# Controller.net
KiCad netlist of a schematic drawn in Altium Designer
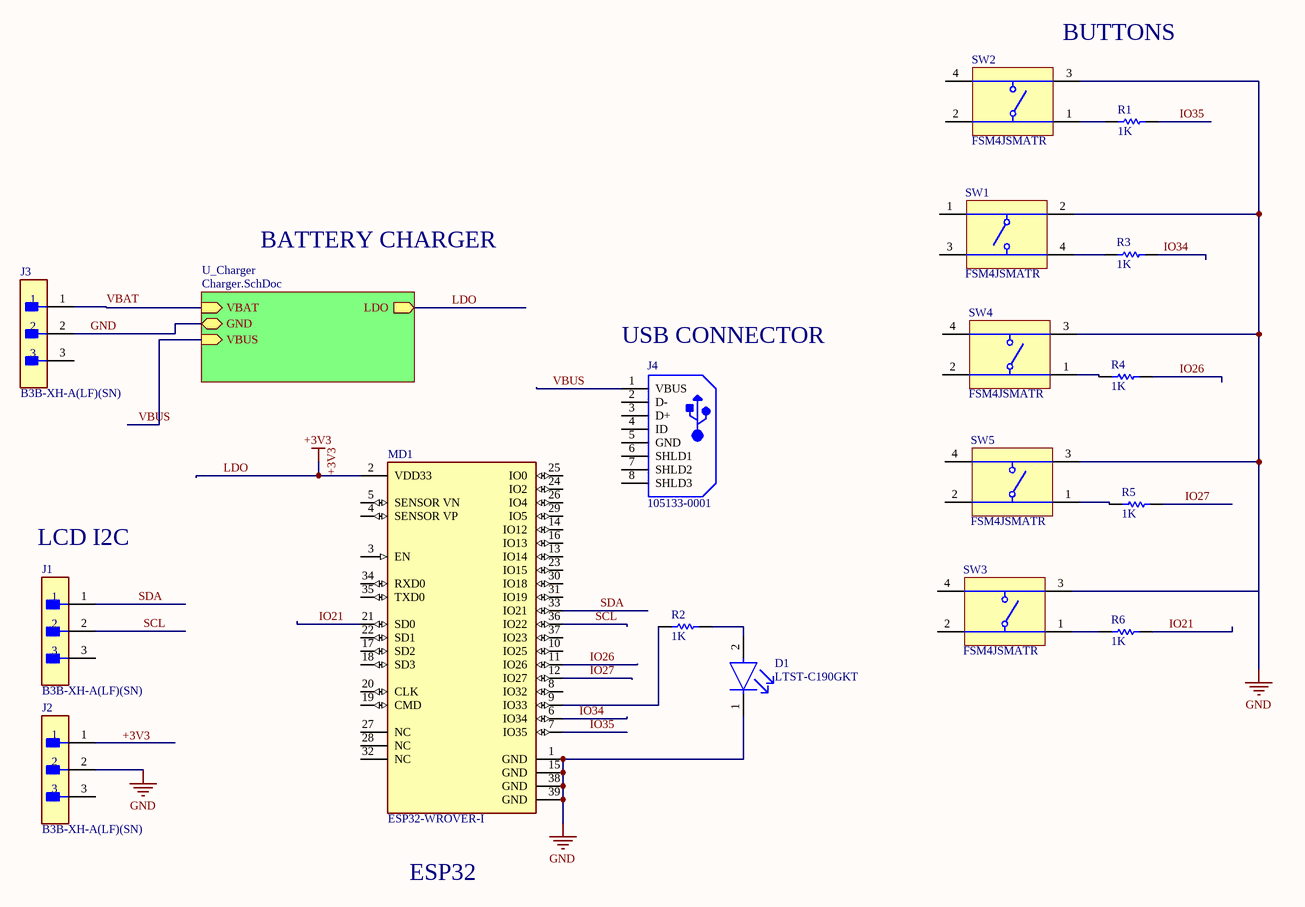
[diagram p0: Controller.SchDoc]

(export (version "E")
  (design (tool "Eeschema 10.0.6"))
  (components
    (comp (ref "D1")
      (value "LTST-C190GKT")
      (footprint "FP-LTST-C190GKT-MFG")
      (description "LED GREEN CLEAR CHIP SMD")
      (fields (field (name "VOLTAGE") "2V"))
      (libsource (lib "Altium Content Vault") (part "8706943c75ba83719d021d2fdc84c58"))
    )
    (comp (ref "J1")
      (value "B3B-XH-A(LF)(SN)")
      (footprint "FP-B3B-XH-A_LF_SN-MFG")
      (description "CONN HEADER VERT 3POS 2.5MM")
      (libsource (lib "Altium Content Vault") (part "0d3f023dd272f625e17a2be33dea85f"))
    )
    (comp (ref "J2")
      (value "B3B-XH-A(LF)(SN)")
      (footprint "FP-B3B-XH-A_LF_SN-MFG")
      (description "CONN HEADER VERT 3POS 2.5MM")
      (libsource (lib "Altium Content Vault") (part "0d3f023dd272f625e17a2be33dea85f"))
    )
    (comp (ref "J3")
      (value "B3B-XH-A(LF)(SN)")
      (footprint "FP-B3B-XH-A_LF_SN-MFG")
      (description "CONN HEADER VERT 3POS 2.5MM")
      (libsource (lib "Altium Content Vault") (part "0d3f023dd272f625e17a2be33dea85f"))
    )
    (comp (ref "J4")
      (value "105133-0001")
      (footprint "MOLX-105133-0001_V")
      (description "Micro-USB B Receptacle, Vertical, -30 to 85 degC, 5-Pin SMD, RoHS, Tape and Reel")
      (fields (field (name "MANUFACTURER") "Molex"))
      (libsource (lib "Altium Content Vault") (part "USB-5-3SHLD"))
    )
    (comp (ref "MD1")
      (value "ESP32-WROVER-I")
      (footprint "FP-ESP32-WROVER-I-MFG")
      (description "SMD MODULE, ESP32-D0WDQ6, 32MBIT")
      (fields
        (field (name "MANUFACTURER") "Espressif")
        (field (name "OCTOPART") "https://octopart.com/esp32-wrover-i-espressif+systems-89171349")
      )
      (libsource (lib "Altium Content Vault") (part "cbbb37af8bcfe61dfd46ac9418f0340"))
    )
    (comp (ref "R1")
      (value "1K")
      (footprint "RESC2013X65X40LL15T20")
      (description "Chip Resistor, 0 Ohm, 0.125 W, -55 to 125 degC, 0805 (2012 Metric), RoHS, Tape and Reel")
      (fields (field (name "TOLERANCE") "0%") (field (name "MANUFACTURER") "TE Connectivity"))
      (libsource (lib "Altium Content Vault") (part "RES-2"))
    )
    (comp (ref "R2")
      (value "1K")
      (footprint "RESC2013X65X40LL15T20")
      (description "Chip Resistor, 0 Ohm, 0.125 W, -55 to 125 degC, 0805 (2012 Metric), RoHS, Tape and Reel")
      (fields (field (name "TOLERANCE") "0%") (field (name "MANUFACTURER") "TE Connectivity"))
      (libsource (lib "Altium Content Vault") (part "RES-2"))
    )
    (comp (ref "R3")
      (value "1K")
      (footprint "RESC2013X65X40LL15T20")
      (description "Chip Resistor, 0 Ohm, 0.125 W, -55 to 125 degC, 0805 (2012 Metric), RoHS, Tape and Reel")
      (fields (field (name "TOLERANCE") "0%") (field (name "MANUFACTURER") "TE Connectivity"))
      (libsource (lib "Altium Content Vault") (part "RES-2"))
    )
    (comp (ref "R4")
      (value "1K")
      (footprint "RESC2013X65X40LL15T20")
      (description "Chip Resistor, 0 Ohm, 0.125 W, -55 to 125 degC, 0805 (2012 Metric), RoHS, Tape and Reel")
      (fields (field (name "TOLERANCE") "0%") (field (name "MANUFACTURER") "TE Connectivity"))
      (libsource (lib "Altium Content Vault") (part "RES-2"))
    )
    (comp (ref "R5")
      (value "1K")
      (footprint "RESC2013X65X40LL15T20")
      (description "Chip Resistor, 0 Ohm, 0.125 W, -55 to 125 degC, 0805 (2012 Metric), RoHS, Tape and Reel")
      (fields (field (name "TOLERANCE") "0%") (field (name "MANUFACTURER") "TE Connectivity"))
      (libsource (lib "Altium Content Vault") (part "RES-2"))
    )
    (comp (ref "R6")
      (value "1K")
      (footprint "RESC2013X65X40LL15T20")
      (description "Chip Resistor, 0 Ohm, 0.125 W, -55 to 125 degC, 0805 (2012 Metric), RoHS, Tape and Reel")
      (fields (field (name "TOLERANCE") "0%") (field (name "MANUFACTURER") "TE Connectivity"))
      (libsource (lib "Altium Content Vault") (part "RES-2"))
    )
    (comp (ref "SW1")
      (value "FSM4JSMATR")
      (footprint "TECO-FSM4JSMATR_V")
      (description "Micro Miniature Push Button Switch FSM JSM, 50 mA, -35 to 85 degC, 4-Pin SMD, RoHS, Tape and Reel")
      (fields (field (name "MANUFACTURER") "TE Connectivity"))
      (libsource (lib "") (part "SW-SPST-4_A_1"))
    )
    (comp (ref "SW2")
      (value "FSM4JSMATR")
      (footprint "TECO-FSM4JSMATR_V")
      (description "Micro Miniature Push Button Switch FSM JSM, 50 mA, -35 to 85 degC, 4-Pin SMD, RoHS, Tape and Reel")
      (fields (field (name "MANUFACTURER") "TE Connectivity"))
      (libsource (lib "Altium Content Vault") (part "SW-SPST-4_A"))
    )
    (comp (ref "SW3")
      (value "FSM4JSMATR")
      (footprint "TECO-FSM4JSMATR_V")
      (description "Micro Miniature Push Button Switch FSM JSM, 50 mA, -35 to 85 degC, 4-Pin SMD, RoHS, Tape and Reel")
      (fields (field (name "MANUFACTURER") "TE Connectivity"))
      (libsource (lib "Altium Content Vault") (part "SW-SPST-4_A"))
    )
    (comp (ref "SW4")
      (value "FSM4JSMATR")
      (footprint "TECO-FSM4JSMATR_V")
      (description "Micro Miniature Push Button Switch FSM JSM, 50 mA, -35 to 85 degC, 4-Pin SMD, RoHS, Tape and Reel")
      (fields (field (name "MANUFACTURER") "TE Connectivity"))
      (libsource (lib "Altium Content Vault") (part "SW-SPST-4_A"))
    )
    (comp (ref "SW5")
      (value "FSM4JSMATR")
      (footprint "TECO-FSM4JSMATR_V")
      (description "Micro Miniature Push Button Switch FSM JSM, 50 mA, -35 to 85 degC, 4-Pin SMD, RoHS, Tape and Reel")
      (fields (field (name "MANUFACTURER") "TE Connectivity"))
      (libsource (lib "Altium Content Vault") (part "SW-SPST-4_A"))
    )
  )
  (nets
    (net (code "1") (name "+3V3") (class "Default")
      (node (ref "MD1") (pin "2") (pinfunction "VDD33_2") (pintype "power_in"))
    )
    (net (code "2") (name "/IO21") (class "Default")
      (node (ref "MD1") (pin "21") (pinfunction "SD0_21") (pintype "bidirectional"))
      (node (ref "R6") (pin "1") (pinfunction "1_1") (pintype "passive"))
    )
    (net (code "3") (name "/IO26") (class "Default")
      (node (ref "MD1") (pin "11") (pinfunction "IO26_11") (pintype "bidirectional"))
      (node (ref "R4") (pin "1") (pinfunction "1_1") (pintype "passive"))
    )
    (net (code "4") (name "/IO27") (class "Default")
      (node (ref "MD1") (pin "12") (pinfunction "IO27_12") (pintype "bidirectional"))
      (node (ref "R5") (pin "1") (pinfunction "1_1") (pintype "passive"))
    )
    (net (code "5") (name "/IO34") (class "Default")
      (node (ref "MD1") (pin "6") (pinfunction "IO34_6") (pintype "bidirectional"))
      (node (ref "R3") (pin "1") (pinfunction "1_1") (pintype "passive"))
    )
    (net (code "6") (name "/IO35") (class "Default")
      (node (ref "MD1") (pin "7") (pinfunction "IO35_7") (pintype "bidirectional"))
      (node (ref "R1") (pin "1") (pinfunction "1_1") (pintype "passive"))
    )
    (net (code "7") (name "/SCL") (class "Default")
      (node (ref "J1") (pin "2") (pinfunction "2_2") (pintype "passive"))
      (node (ref "MD1") (pin "36") (pinfunction "IO22_36") (pintype "bidirectional"))
    )
    (net (code "8") (name "/SDA") (class "Default")
      (node (ref "J1") (pin "1") (pinfunction "1_1") (pintype "passive"))
      (node (ref "MD1") (pin "33") (pinfunction "IO21_33") (pintype "bidirectional"))
    )
    (net (code "9") (name "/VBAT") (class "Default")
      (node (ref "J3") (pin "1") (pinfunction "1_1") (pintype "passive"))
    )
    (net (code "10") (name "/VBUS") (class "Default")
      (node (ref "J4") (pin "1") (pinfunction "VBUS_1") (pintype "passive"))
    )
    (net (code "11") (name "GND") (class "Default")
      (node (ref "D1") (pin "1") (pinfunction "C_1") (pintype "passive"))
      (node (ref "J2") (pin "2") (pinfunction "2_2") (pintype "passive"))
      (node (ref "J3") (pin "2") (pinfunction "2_2") (pintype "passive"))
      (node (ref "MD1") (pin "1") (pinfunction "GND_1") (pintype "power_in"))
      (node (ref "MD1") (pin "15") (pinfunction "GND_15") (pintype "power_in"))
      (node (ref "MD1") (pin "38") (pinfunction "GND_38") (pintype "power_in"))
      (node (ref "MD1") (pin "39") (pinfunction "GND_39") (pintype "power_in"))
      (node (ref "SW1") (pin "2") (pinfunction "2_2") (pintype "passive"))
      (node (ref "SW2") (pin "3") (pinfunction "3_3") (pintype "passive"))
      (node (ref "SW4") (pin "3") (pinfunction "3_3") (pintype "passive"))
      (node (ref "SW5") (pin "3") (pinfunction "3_3") (pintype "passive"))
    )
    (net (code "12") (name "Net-(D1-A)") (class "Default")
      (node (ref "D1") (pin "2") (pinfunction "A_2") (pintype "passive"))
      (node (ref "R2") (pin "2") (pinfunction "2_2") (pintype "passive"))
    )
    (net (code "13") (name "Net-(MD1-IO33)") (class "Default")
      (node (ref "MD1") (pin "9") (pinfunction "IO33_9") (pintype "bidirectional"))
      (node (ref "R2") (pin "1") (pinfunction "1_1") (pintype "passive"))
    )
    (net (code "14") (name "Net-(R1-Pad2)") (class "Default")
      (node (ref "R1") (pin "2") (pinfunction "2_2") (pintype "passive"))
      (node (ref "SW2") (pin "1") (pinfunction "1_1") (pintype "passive"))
    )
    (net (code "15") (name "Net-(R3-Pad2)") (class "Default")
      (node (ref "R3") (pin "2") (pinfunction "2_2") (pintype "passive"))
      (node (ref "SW1") (pin "4") (pinfunction "4_4") (pintype "passive"))
    )
    (net (code "16") (name "Net-(R4-Pad2)") (class "Default")
      (node (ref "R4") (pin "2") (pinfunction "2_2") (pintype "passive"))
      (node (ref "SW4") (pin "1") (pinfunction "1_1") (pintype "passive"))
    )
    (net (code "17") (name "Net-(R5-Pad2)") (class "Default")
      (node (ref "R5") (pin "2") (pinfunction "2_2") (pintype "passive"))
      (node (ref "SW5") (pin "1") (pinfunction "1_1") (pintype "passive"))
    )
    (net (code "18") (name "Net-(R6-Pad2)") (class "Default")
      (node (ref "R6") (pin "2") (pinfunction "2_2") (pintype "passive"))
      (node (ref "SW3") (pin "1") (pinfunction "1_1") (pintype "passive"))
    )
    (net (code "19") (name "unconnected-(J1-Pad3)") (class "Default")
      (node (ref "J1") (pin "3") (pinfunction "3_3") (pintype "passive"))
    )
    (net (code "20") (name "unconnected-(J2-Pad1)") (class "Default")
      (node (ref "J2") (pin "1") (pinfunction "1_1") (pintype "passive"))
    )
    (net (code "21") (name "unconnected-(J2-Pad3)") (class "Default")
      (node (ref "J2") (pin "3") (pinfunction "3_3") (pintype "passive"))
    )
    (net (code "22") (name "unconnected-(J3-Pad3)") (class "Default")
      (node (ref "J3") (pin "3") (pinfunction "3_3") (pintype "passive"))
    )
    (net (code "23") (name "unconnected-(J4-D+-Pad3)") (class "Default")
      (node (ref "J4") (pin "3") (pinfunction "D+_3") (pintype "passive"))
    )
    (net (code "24") (name "unconnected-(J4-D--Pad2)") (class "Default")
      (node (ref "J4") (pin "2") (pinfunction "D-_2") (pintype "passive"))
    )
    (net (code "25") (name "unconnected-(J4-GND-Pad5)") (class "Default")
      (node (ref "J4") (pin "5") (pinfunction "GND_5") (pintype "passive"))
    )
    (net (code "26") (name "unconnected-(J4-ID-Pad4)") (class "Default")
      (node (ref "J4") (pin "4") (pinfunction "ID_4") (pintype "passive"))
    )
    (net (code "27") (name "unconnected-(J4-SHLD1-Pad6)") (class "Default")
      (node (ref "J4") (pin "6") (pinfunction "SHLD1_6") (pintype "passive"))
    )
    (net (code "28") (name "unconnected-(J4-SHLD2-Pad7)") (class "Default")
      (node (ref "J4") (pin "7") (pinfunction "SHLD2_7") (pintype "passive"))
    )
    (net (code "29") (name "unconnected-(J4-SHLD3-Pad8)") (class "Default")
      (node (ref "J4") (pin "8") (pinfunction "SHLD3_8") (pintype "passive"))
    )
    (net (code "30") (name "unconnected-(MD1-CLK-Pad20)") (class "Default")
      (node (ref "MD1") (pin "20") (pinfunction "CLK_20") (pintype "bidirectional"))
    )
    (net (code "31") (name "unconnected-(MD1-CMD-Pad19)") (class "Default")
      (node (ref "MD1") (pin "19") (pinfunction "CMD_19") (pintype "bidirectional"))
    )
    (net (code "32") (name "unconnected-(MD1-EN-Pad3)") (class "Default")
      (node (ref "MD1") (pin "3") (pinfunction "EN_3") (pintype "input"))
    )
    (net (code "33") (name "unconnected-(MD1-IO0-Pad25)") (class "Default")
      (node (ref "MD1") (pin "25") (pinfunction "IO0_25") (pintype "bidirectional"))
    )
    (net (code "34") (name "unconnected-(MD1-IO2-Pad24)") (class "Default")
      (node (ref "MD1") (pin "24") (pinfunction "IO2_24") (pintype "bidirectional"))
    )
    (net (code "35") (name "unconnected-(MD1-IO4-Pad26)") (class "Default")
      (node (ref "MD1") (pin "26") (pinfunction "IO4_26") (pintype "bidirectional"))
    )
    (net (code "36") (name "unconnected-(MD1-IO5-Pad29)") (class "Default")
      (node (ref "MD1") (pin "29") (pinfunction "IO5_29") (pintype "bidirectional"))
    )
    (net (code "37") (name "unconnected-(MD1-IO12-Pad14)") (class "Default")
      (node (ref "MD1") (pin "14") (pinfunction "IO12_14") (pintype "bidirectional"))
    )
    (net (code "38") (name "unconnected-(MD1-IO13-Pad16)") (class "Default")
      (node (ref "MD1") (pin "16") (pinfunction "IO13_16") (pintype "bidirectional"))
    )
    (net (code "39") (name "unconnected-(MD1-IO14-Pad13)") (class "Default")
      (node (ref "MD1") (pin "13") (pinfunction "IO14_13") (pintype "bidirectional"))
    )
    (net (code "40") (name "unconnected-(MD1-IO15-Pad23)") (class "Default")
      (node (ref "MD1") (pin "23") (pinfunction "IO15_23") (pintype "bidirectional"))
    )
    (net (code "41") (name "unconnected-(MD1-IO18-Pad30)") (class "Default")
      (node (ref "MD1") (pin "30") (pinfunction "IO18_30") (pintype "bidirectional"))
    )
    (net (code "42") (name "unconnected-(MD1-IO19-Pad31)") (class "Default")
      (node (ref "MD1") (pin "31") (pinfunction "IO19_31") (pintype "bidirectional"))
    )
    (net (code "43") (name "unconnected-(MD1-IO23-Pad37)") (class "Default")
      (node (ref "MD1") (pin "37") (pinfunction "IO23_37") (pintype "bidirectional"))
    )
    (net (code "44") (name "unconnected-(MD1-IO25-Pad10)") (class "Default")
      (node (ref "MD1") (pin "10") (pinfunction "IO25_10") (pintype "bidirectional"))
    )
    (net (code "45") (name "unconnected-(MD1-IO32-Pad8)") (class "Default")
      (node (ref "MD1") (pin "8") (pinfunction "IO32_8") (pintype "bidirectional"))
    )
    (net (code "46") (name "unconnected-(MD1-NC-Pad27)") (class "Default")
      (node (ref "MD1") (pin "27") (pinfunction "NC_27") (pintype "passive"))
    )
    (net (code "47") (name "unconnected-(MD1-NC-Pad28)") (class "Default")
      (node (ref "MD1") (pin "28") (pinfunction "NC_28") (pintype "passive"))
    )
    (net (code "48") (name "unconnected-(MD1-NC-Pad32)") (class "Default")
      (node (ref "MD1") (pin "32") (pinfunction "NC_32") (pintype "passive"))
    )
    (net (code "49") (name "unconnected-(MD1-RXD0-Pad34)") (class "Default")
      (node (ref "MD1") (pin "34") (pinfunction "RXD0_34") (pintype "bidirectional"))
    )
    (net (code "50") (name "unconnected-(MD1-SD1-Pad22)") (class "Default")
      (node (ref "MD1") (pin "22") (pinfunction "SD1_22") (pintype "bidirectional"))
    )
    (net (code "51") (name "unconnected-(MD1-SD2-Pad17)") (class "Default")
      (node (ref "MD1") (pin "17") (pinfunction "SD2_17") (pintype "bidirectional"))
    )
    (net (code "52") (name "unconnected-(MD1-SD3-Pad18)") (class "Default")
      (node (ref "MD1") (pin "18") (pinfunction "SD3_18") (pintype "bidirectional"))
    )
    (net (code "53") (name "unconnected-(MD1-SENSOR_VN-Pad5)") (class "Default")
      (node (ref "MD1") (pin "5") (pinfunction "SENSOR_VN_5") (pintype "bidirectional"))
    )
    (net (code "54") (name "unconnected-(MD1-SENSOR_VP-Pad4)") (class "Default")
      (node (ref "MD1") (pin "4") (pinfunction "SENSOR_VP_4") (pintype "bidirectional"))
    )
    (net (code "55") (name "unconnected-(MD1-TXD0-Pad35)") (class "Default")
      (node (ref "MD1") (pin "35") (pinfunction "TXD0_35") (pintype "bidirectional"))
    )
    (net (code "56") (name "unconnected-(SW1-Pad1)") (class "Default")
      (node (ref "SW1") (pin "1") (pinfunction "1_1") (pintype "passive"))
    )
    (net (code "57") (name "unconnected-(SW1-Pad3)") (class "Default")
      (node (ref "SW1") (pin "3") (pinfunction "3_3") (pintype "passive"))
    )
    (net (code "58") (name "unconnected-(SW2-Pad2)") (class "Default")
      (node (ref "SW2") (pin "2") (pinfunction "2_2") (pintype "passive"))
    )
    (net (code "59") (name "unconnected-(SW2-Pad4)") (class "Default")
      (node (ref "SW2") (pin "4") (pinfunction "4_4") (pintype "passive"))
    )
    (net (code "60") (name "unconnected-(SW3-Pad2)") (class "Default")
      (node (ref "SW3") (pin "2") (pinfunction "2_2") (pintype "passive"))
    )
    (net (code "61") (name "unconnected-(SW3-Pad3)") (class "Default")
      (node (ref "SW3") (pin "3") (pinfunction "3_3") (pintype "passive"))
    )
    (net (code "62") (name "unconnected-(SW3-Pad4)") (class "Default")
      (node (ref "SW3") (pin "4") (pinfunction "4_4") (pintype "passive"))
    )
    (net (code "63") (name "unconnected-(SW4-Pad2)") (class "Default")
      (node (ref "SW4") (pin "2") (pinfunction "2_2") (pintype "passive"))
    )
    (net (code "64") (name "unconnected-(SW4-Pad4)") (class "Default")
      (node (ref "SW4") (pin "4") (pinfunction "4_4") (pintype "passive"))
    )
    (net (code "65") (name "unconnected-(SW5-Pad2)") (class "Default")
      (node (ref "SW5") (pin "2") (pinfunction "2_2") (pintype "passive"))
    )
    (net (code "66") (name "unconnected-(SW5-Pad4)") (class "Default")
      (node (ref "SW5") (pin "4") (pinfunction "4_4") (pintype "passive"))
    )
  )
)
